# 4_unextended_ANSI_power.net
KiCad netlist of a schematic drawn in Altium Designer
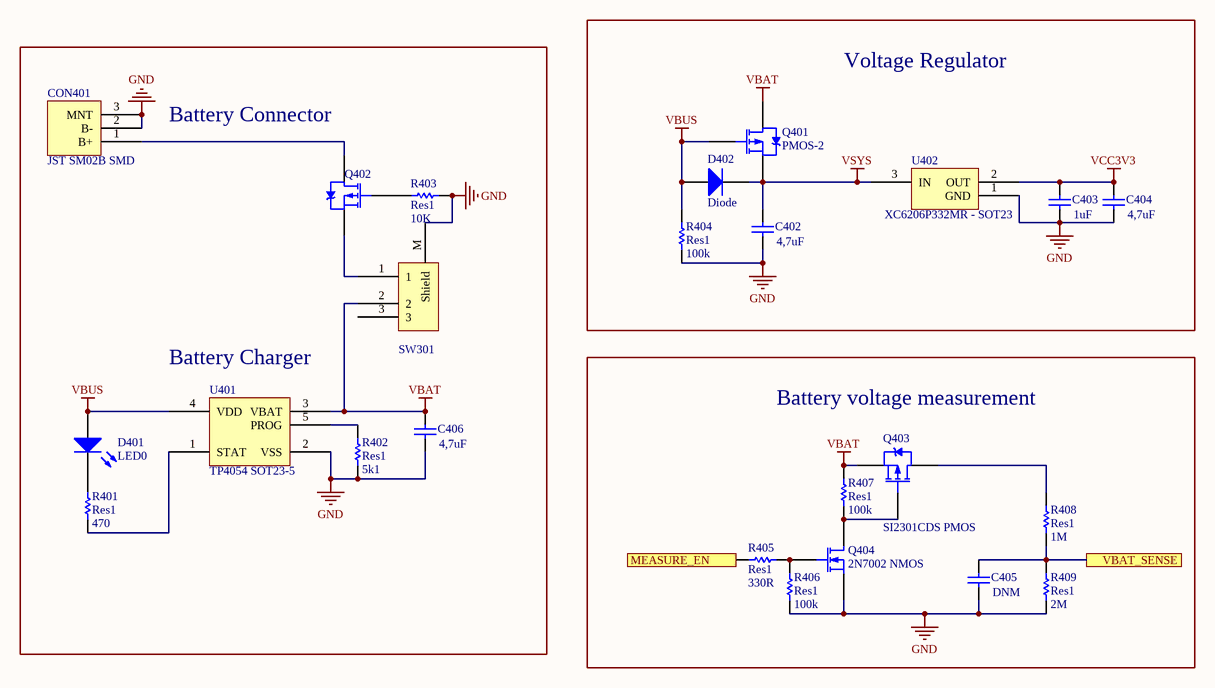
[diagram p0: 4_unextended_ANSI_power.SchDoc]

(export (version "E")
  (design (tool "Eeschema 10.0.6"))
  (components
    (comp (ref "C402")
      (value "4,7uF")
      (footprint "C0603[1608]")
      (description "Capacitor")
      (fields (field (name "LCSC PART #") "C19666") (field (name "MRF.PART") "CL10A475KO8NNNC"))
      (libsource (lib "Miscellaneous Devices") (part "Cap"))
    )
    (comp (ref "C403")
      (value "1uF")
      (footprint "C0603[1608]")
      (description "Capacitor")
      (fields (field (name "MFG") "KEMET") (field (name "LCSC PART #") "C15849"))
      (libsource (lib "Miscellaneous Devices") (part "Cap"))
    )
    (comp (ref "C404")
      (value "4,7uF")
      (footprint "C0603[1608]")
      (description "Capacitor")
      (fields (field (name "LCSC PART #") "C19666") (field (name "MRF.PART") "CL10A475KO8NNNC"))
      (libsource (lib "Miscellaneous Devices") (part "Cap"))
    )
    (comp (ref "C405")
      (value "DNM")
      (footprint "C0603[1608]")
      (description "Capacitor")
      (libsource (lib "Miscellaneous Devices") (part "Cap"))
    )
    (comp (ref "C406")
      (value "4,7uF")
      (footprint "C0603[1608]")
      (description "Capacitor")
      (fields (field (name "LCSC PART #") "C19666") (field (name "MRF.PART") "CL10A475KO8NNNC"))
      (libsource (lib "Miscellaneous Devices") (part "Cap"))
    )
    (comp (ref "CON401")
      (value "JST SM02B SMD")
      (footprint "JST S2B-PH-SM4-TB")
      (libsource (lib "Keebs") (part "JST S2B-PH-SM4-TB"))
    )
    (comp (ref "D401")
      (value "LED0")
      (footprint "LED0603[1608]")
      (description "Typical INFRARED GaAs LED")
      (fields (field (name "LCSC PART #") "C72038") (field (name "MRF.PART") "19-213/Y2C-CQ2R2L/3T(CY)"))
      (libsource (lib "Miscellaneous Devices") (part "LED0"))
    )
    (comp (ref "D402")
      (value "Diode")
      (footprint "SOD-123")
      (description "Default Diode")
      (fields (field (name "LCSC PART #") "C8598") (field (name "MRF.PART") "B5819W"))
      (libsource (lib "Miscellaneous Devices") (part "Diode"))
    )
    (comp (ref "Q401")
      (value "PMOS-2")
      (footprint "SOT-23-3")
      (description "P-Channel Power MOSFET")
      (fields (field (name "MRF.PART") "SI2301CDS-T1-GE3") (field (name "LCSC PART #") "C10487"))
      (libsource (lib "Miscellaneous Devices") (part "PMOS-2"))
    )
    (comp (ref "Q402")
      (value "PMOS-2")
      (footprint "SOT-23-3")
      (description "P-Channel Power MOSFET")
      (fields (field (name "LCSC PART #") "C10487") (field (name "MRF.PART") "SI2301CDS-T1-GE3"))
      (libsource (lib "Miscellaneous Devices") (part "PMOS-2"))
    )
    (comp (ref "Q403")
      (value "SI2301CDS PMOS")
      (footprint "SOT-23-3")
      (description "P-Channel Power MOSFET")
      (fields (field (name "MRF.PART") "SI2301CDS-T1-GE3") (field (name "LCSC PART #") "C10487"))
      (libsource (lib "Miscellaneous Devices") (part "PMOS-2"))
    )
    (comp (ref "Q404")
      (value "2N7002 NMOS")
      (footprint "SOT-23-3")
      (description "N-Channel MOSFET")
      (fields (field (name "LCSC PART #") "C8545") (field (name "MRF.PART") "2N7002"))
      (libsource (lib "Miscellaneous Devices") (part "MOSFET-N"))
    )
    (comp (ref "R401")
      (value "Res1")
      (footprint "R0603[1608]")
      (description "Resistor")
      (fields
        (field (name "ALTIUM_VALUE") "470")
        (field (name "MFG") "Panasonic Electronic Components")
        (field (name "LCSC PART #") "C23179")
      )
      (libsource (lib "Miscellaneous Devices") (part "Res1"))
    )
    (comp (ref "R402")
      (value "Res1")
      (footprint "R0603[1608]")
      (description "Resistor")
      (fields
        (field (name "ALTIUM_VALUE") "5k1")
        (field (name "MFG") "Panasonic Electronic Components")
        (field (name "LCSC PART #") "C23186")
      )
      (libsource (lib "Miscellaneous Devices") (part "Res1"))
    )
    (comp (ref "R403")
      (value "Res1")
      (footprint "R0603[1608]")
      (description "Resistor")
      (fields
        (field (name "ALTIUM_VALUE") "10K")
        (field (name "MFG") "Panasonic Electronic Components")
        (field (name "LCSC PART #") "C25804")
      )
      (libsource (lib "Miscellaneous Devices") (part "Res1"))
    )
    (comp (ref "R404")
      (value "Res1")
      (footprint "R0603[1608]")
      (description "Resistor")
      (fields
        (field (name "ALTIUM_VALUE") "100k")
        (field (name "MRF.PART") "0603WAF1003T5E")
        (field (name "LCSC PART #") "C25803")
      )
      (libsource (lib "Miscellaneous Devices") (part "Res1"))
    )
    (comp (ref "R405")
      (value "Res1")
      (footprint "R0603[1608]")
      (description "Resistor")
      (fields
        (field (name "ALTIUM_VALUE") "330R")
        (field (name "LCSC PART #") "C23138")
        (field (name "MRF.PART") "0603WAF3300T5E")
      )
      (libsource (lib "Miscellaneous Devices") (part "Res1"))
    )
    (comp (ref "R406")
      (value "Res1")
      (footprint "R0603[1608]")
      (description "Resistor")
      (fields
        (field (name "ALTIUM_VALUE") "100k")
        (field (name "MRF.PART") "0603WAF1003T5E")
        (field (name "LCSC PART #") "C25803")
      )
      (libsource (lib "Miscellaneous Devices") (part "Res1"))
    )
    (comp (ref "R407")
      (value "Res1")
      (footprint "R0603[1608]")
      (description "Resistor")
      (fields
        (field (name "ALTIUM_VALUE") "100k")
        (field (name "MRF.PART") "0603WAF1003T5E")
        (field (name "LCSC PART #") "C25803")
      )
      (libsource (lib "Miscellaneous Devices") (part "Res1"))
    )
    (comp (ref "R408")
      (value "Res1")
      (footprint "R0603[1608]")
      (description "Resistor")
      (fields
        (field (name "ALTIUM_VALUE") "1M")
        (field (name "MRF.PART") "0603WAF1004T5E")
        (field (name "LCSC PART #") "C22935")
      )
      (libsource (lib "Miscellaneous Devices") (part "Res1"))
    )
    (comp (ref "R409")
      (value "Res1")
      (footprint "R0603[1608]")
      (description "Resistor")
      (fields
        (field (name "ALTIUM_VALUE") "2M")
        (field (name "MRF.PART") "0603WAF2004T5E")
        (field (name "LCSC PART #") "C22976")
      )
      (libsource (lib "Miscellaneous Devices") (part "Res1"))
    )
    (comp (ref "SW301")
      (value "Korean Hroparts Elec K3-1296S-E2")
      (footprint "Korean Hroparts Elec K3-1296S-E2")
      (fields (field (name "LCSC PART #") "C136659"))
      (libsource (lib "Keebs") (part "Korean Hroparts Elec K3-1296S-E2"))
    )
    (comp (ref "U401")
      (value "TP4054 SOT23-5")
      (footprint "SOT-23-5")
      (fields (field (name "LCSC PART #") "C32574") (field (name "MRF.PART") "TP4054"))
      (libsource (lib "Keebs") (part "MCP73831"))
    )
    (comp (ref "U402")
      (value "XC6206P332MR - SOT23")
      (footprint "SOT-23-3")
      (fields
        (field (name "LCSC PART #") "C5446")
        (field (name "MRF.PART") "XC6206P332MR")
        (field (name "MFG") "Texas Instruments")
      )
      (libsource (lib "Keebs") (part "SOT23 LDO"))
    )
  )
  (nets
    (net (code "1") (name "/MEASURE_EN") (class "Default")
      (node (ref "R405") (pin "1") (pinfunction "1_1") (pintype "passive"))
    )
    (net (code "2") (name "/VBAT_SENSE") (class "Default")
      (node (ref "C405") (pin "2") (pinfunction "2_2") (pintype "passive"))
      (node (ref "R408") (pin "2") (pinfunction "2_2") (pintype "passive"))
      (node (ref "R409") (pin "1") (pinfunction "1_1") (pintype "passive"))
    )
    (net (code "3") (name "GND") (class "Default")
      (node (ref "C402") (pin "1") (pinfunction "1_1") (pintype "passive"))
      (node (ref "C403") (pin "1") (pinfunction "1_1") (pintype "passive"))
      (node (ref "C404") (pin "1") (pinfunction "1_1") (pintype "passive"))
      (node (ref "C405") (pin "1") (pinfunction "1_1") (pintype "passive"))
      (node (ref "C406") (pin "1") (pinfunction "1_1") (pintype "passive"))
      (node (ref "CON401") (pin "2") (pinfunction "B-_2") (pintype "passive"))
      (node (ref "CON401") (pin "3") (pinfunction "MNT_3") (pintype "passive"))
      (node (ref "Q404") (pin "2") (pinfunction "S_2") (pintype "passive"))
      (node (ref "R402") (pin "2") (pinfunction "2_2") (pintype "passive"))
      (node (ref "R403") (pin "2") (pinfunction "2_2") (pintype "passive"))
      (node (ref "R404") (pin "2") (pinfunction "2_2") (pintype "passive"))
      (node (ref "R406") (pin "2") (pinfunction "2_2") (pintype "passive"))
      (node (ref "R409") (pin "2") (pinfunction "2_2") (pintype "passive"))
      (node (ref "SW301") (pin "M") (pinfunction "Shield_M") (pintype "passive"))
      (node (ref "U401") (pin "2") (pinfunction "VSS_2") (pintype "passive"))
      (node (ref "U402") (pin "1") (pinfunction "GND_1") (pintype "passive"))
    )
    (net (code "4") (name "Net-(CON401-B+)") (class "Default")
      (node (ref "CON401") (pin "1") (pinfunction "B+_1") (pintype "passive"))
      (node (ref "Q402") (pin "3") (pinfunction "D_3") (pintype "passive"))
    )
    (net (code "5") (name "Net-(D401-K)") (class "Default")
      (node (ref "D401") (pin "2") (pinfunction "K_2") (pintype "passive"))
      (node (ref "R401") (pin "2") (pinfunction "2_2") (pintype "passive"))
    )
    (net (code "6") (name "Net-(Q402-G)") (class "Default")
      (node (ref "Q402") (pin "1") (pinfunction "G_1") (pintype "passive"))
      (node (ref "R403") (pin "1") (pinfunction "1_1") (pintype "passive"))
    )
    (net (code "7") (name "Net-(Q402-S)") (class "Default")
      (node (ref "Q402") (pin "2") (pinfunction "S_2") (pintype "passive"))
      (node (ref "SW301") (pin "1") (pinfunction "1_1") (pintype "passive"))
    )
    (net (code "8") (name "Net-(Q403-D)") (class "Default")
      (node (ref "Q403") (pin "3") (pinfunction "D_3") (pintype "passive"))
      (node (ref "R408") (pin "1") (pinfunction "1_1") (pintype "passive"))
    )
    (net (code "9") (name "Net-(Q403-G)") (class "Default")
      (node (ref "Q403") (pin "1") (pinfunction "G_1") (pintype "passive"))
      (node (ref "Q404") (pin "3") (pinfunction "D_3") (pintype "passive"))
      (node (ref "R407") (pin "2") (pinfunction "2_2") (pintype "passive"))
    )
    (net (code "10") (name "Net-(Q404-G)") (class "Default")
      (node (ref "Q404") (pin "1") (pinfunction "G_1") (pintype "passive"))
      (node (ref "R405") (pin "2") (pinfunction "2_2") (pintype "passive"))
      (node (ref "R406") (pin "1") (pinfunction "1_1") (pintype "passive"))
    )
    (net (code "11") (name "Net-(U401-PROG)") (class "Default")
      (node (ref "R402") (pin "1") (pinfunction "1_1") (pintype "passive"))
      (node (ref "U401") (pin "5") (pinfunction "PROG_5") (pintype "passive"))
    )
    (net (code "12") (name "Net-(U401-STAT)") (class "Default")
      (node (ref "R401") (pin "1") (pinfunction "1_1") (pintype "passive"))
      (node (ref "U401") (pin "1") (pinfunction "STAT_1") (pintype "passive"))
    )
    (net (code "13") (name "VBAT") (class "Default")
      (node (ref "C406") (pin "2") (pinfunction "2_2") (pintype "passive"))
      (node (ref "Q401") (pin "3") (pinfunction "D_3") (pintype "passive"))
      (node (ref "Q403") (pin "2") (pinfunction "S_2") (pintype "passive"))
      (node (ref "R407") (pin "1") (pinfunction "1_1") (pintype "passive"))
      (node (ref "SW301") (pin "2") (pinfunction "2_2") (pintype "passive"))
      (node (ref "U401") (pin "3") (pinfunction "VBAT_3") (pintype "passive"))
    )
    (net (code "14") (name "VBUS") (class "Default")
      (node (ref "D401") (pin "1") (pinfunction "A_1") (pintype "passive"))
      (node (ref "D402") (pin "1") (pinfunction "A_1") (pintype "passive"))
      (node (ref "Q401") (pin "1") (pinfunction "G_1") (pintype "passive"))
      (node (ref "R404") (pin "1") (pinfunction "1_1") (pintype "passive"))
      (node (ref "U401") (pin "4") (pinfunction "VDD_4") (pintype "passive"))
    )
    (net (code "15") (name "VCC3V3") (class "Default")
      (node (ref "C403") (pin "2") (pinfunction "2_2") (pintype "passive"))
      (node (ref "C404") (pin "2") (pinfunction "2_2") (pintype "passive"))
      (node (ref "U402") (pin "2") (pinfunction "OUT_2") (pintype "passive"))
    )
    (net (code "16") (name "VSYS") (class "Default")
      (node (ref "C402") (pin "2") (pinfunction "2_2") (pintype "passive"))
      (node (ref "D402") (pin "2") (pinfunction "K_2") (pintype "passive"))
      (node (ref "Q401") (pin "2") (pinfunction "S_2") (pintype "passive"))
      (node (ref "U402") (pin "3") (pinfunction "IN_3") (pintype "passive"))
    )
    (net (code "17") (name "unconnected-(SW301-Pad3)") (class "Default")
      (node (ref "SW301") (pin "3") (pinfunction "3_3") (pintype "passive"))
    )
  )
)
